# project-nixie.net
KiCad netlist of a schematic drawn in EAGLE
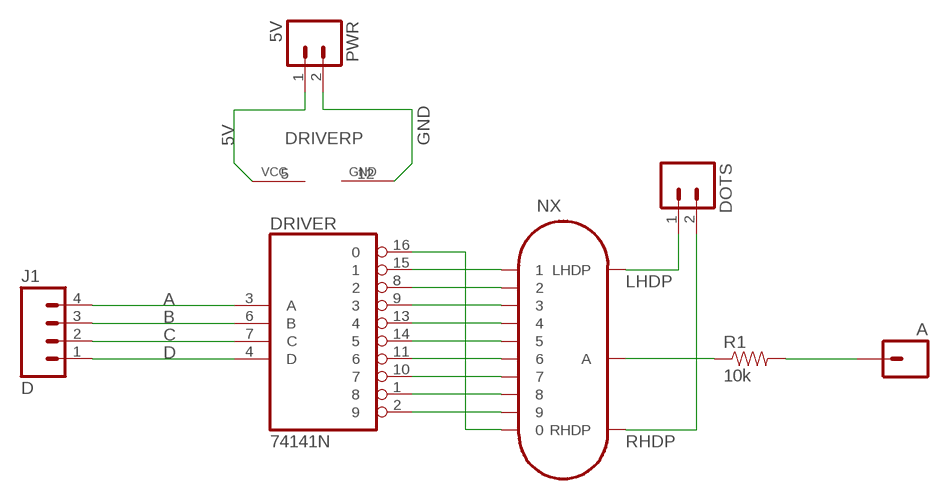
[diagram p0: schematic, sheet 1]

(export (version "E")
  (design (tool "Eeschema 10.0.6"))
  (components
    (comp (ref "A")
      (value "M01PTH")
      (footprint "eagle-import:1X01")
      (libsource (lib "eagle-import") (part "M01PTH"))
    )
    (comp (ref "DOTS")
      (value "M02PTH")
      (footprint "eagle-import:1X02")
      (libsource (lib "eagle-import") (part "M02PTH"))
    )
    (comp (ref "DRIVER")
      (value "74141N")
      (footprint "eagle-import:DIL16")
      (libsource (lib "eagle-import") (part "74141N"))
    )
    (comp (ref "J1")
      (value "D")
      (footprint "eagle-import:1X04_LOCK")
      (libsource (lib "eagle-import") (part "M04LOCK"))
    )
    (comp (ref "NX")
      (value "IN-14")
      (footprint "eagle-import:IN-14")
      (libsource (lib "eagle-import") (part "IN-14"))
    )
    (comp (ref "PWR")
      (value "5V")
      (footprint "eagle-import:1X02_LOCK")
      (libsource (lib "eagle-import") (part "M02LOCK"))
    )
    (comp (ref "R1")
      (value "10k")
      (footprint "eagle-import:AXIAL-0.3")
      (libsource (lib "eagle-import") (part "RESISTORAXIAL-0.3"))
    )
  )
  (nets
    (net (code "1") (name "/5V") (class "Default")
      (node (ref "DRIVER") (pin "5") (pinfunction "VCC_5") (pintype "power_in"))
      (node (ref "PWR") (pin "1") (pinfunction "1_1") (pintype "passive"))
    )
    (net (code "2") (name "/A") (class "Default")
      (node (ref "DRIVER") (pin "3") (pinfunction "A_3") (pintype "input"))
      (node (ref "J1") (pin "4") (pinfunction "4_4") (pintype "passive"))
    )
    (net (code "3") (name "/B") (class "Default")
      (node (ref "DRIVER") (pin "6") (pinfunction "B_6") (pintype "input"))
      (node (ref "J1") (pin "3") (pinfunction "3_3") (pintype "passive"))
    )
    (net (code "4") (name "/C") (class "Default")
      (node (ref "DRIVER") (pin "7") (pinfunction "C_7") (pintype "input"))
      (node (ref "J1") (pin "2") (pinfunction "2_2") (pintype "passive"))
    )
    (net (code "5") (name "/D") (class "Default")
      (node (ref "DRIVER") (pin "4") (pinfunction "D_4") (pintype "input"))
      (node (ref "J1") (pin "1") (pinfunction "1_1") (pintype "passive"))
    )
    (net (code "6") (name "/GND") (class "Default")
      (node (ref "DRIVER") (pin "12") (pinfunction "GND_12") (pintype "power_in"))
      (node (ref "PWR") (pin "2") (pinfunction "2_2") (pintype "passive"))
    )
    (net (code "7") (name "/LHDP") (class "Default")
      (node (ref "DOTS") (pin "1") (pinfunction "1_1") (pintype "passive"))
      (node (ref "NX") (pin "LHDP") (pinfunction "LHDP_LHDP") (pintype "bidirectional"))
    )
    (net (code "8") (name "/RHDP") (class "Default")
      (node (ref "DOTS") (pin "2") (pinfunction "2_2") (pintype "passive"))
      (node (ref "NX") (pin "RHDP") (pinfunction "RHDP_RHDP") (pintype "bidirectional"))
    )
    (net (code "9") (name "Net-(DRIVERA-0)") (class "Default")
      (node (ref "DRIVER") (pin "16") (pinfunction "0_16") (pintype "open_collector"))
      (node (ref "NX") (pin "0") (pinfunction "0_0") (pintype "bidirectional"))
    )
    (net (code "10") (name "Net-(DRIVERA-1)") (class "Default")
      (node (ref "DRIVER") (pin "15") (pinfunction "1_15") (pintype "open_collector"))
      (node (ref "NX") (pin "1") (pinfunction "1_1") (pintype "bidirectional"))
    )
    (net (code "11") (name "Net-(DRIVERA-2)") (class "Default")
      (node (ref "DRIVER") (pin "8") (pinfunction "2_8") (pintype "open_collector"))
      (node (ref "NX") (pin "2") (pinfunction "2_2") (pintype "bidirectional"))
    )
    (net (code "12") (name "Net-(DRIVERA-3)") (class "Default")
      (node (ref "DRIVER") (pin "9") (pinfunction "3_9") (pintype "open_collector"))
      (node (ref "NX") (pin "3") (pinfunction "3_3") (pintype "bidirectional"))
    )
    (net (code "13") (name "Net-(DRIVERA-4)") (class "Default")
      (node (ref "DRIVER") (pin "13") (pinfunction "4_13") (pintype "open_collector"))
      (node (ref "NX") (pin "4") (pinfunction "4_4") (pintype "bidirectional"))
    )
    (net (code "14") (name "Net-(DRIVERA-5)") (class "Default")
      (node (ref "DRIVER") (pin "14") (pinfunction "5_14") (pintype "open_collector"))
      (node (ref "NX") (pin "5") (pinfunction "5_5") (pintype "bidirectional"))
    )
    (net (code "15") (name "Net-(DRIVERA-6)") (class "Default")
      (node (ref "DRIVER") (pin "11") (pinfunction "6_11") (pintype "open_collector"))
      (node (ref "NX") (pin "6") (pinfunction "6_6") (pintype "bidirectional"))
    )
    (net (code "16") (name "Net-(DRIVERA-7)") (class "Default")
      (node (ref "DRIVER") (pin "10") (pinfunction "7_10") (pintype "open_collector"))
      (node (ref "NX") (pin "7") (pinfunction "7_7") (pintype "bidirectional"))
    )
    (net (code "17") (name "Net-(DRIVERA-8)") (class "Default")
      (node (ref "DRIVER") (pin "1") (pinfunction "8_1") (pintype "open_collector"))
      (node (ref "NX") (pin "8") (pinfunction "8_8") (pintype "bidirectional"))
    )
    (net (code "18") (name "Net-(DRIVERA-9)") (class "Default")
      (node (ref "DRIVER") (pin "2") (pinfunction "9_2") (pintype "open_collector"))
      (node (ref "NX") (pin "9") (pinfunction "9_9") (pintype "bidirectional"))
    )
    (net (code "19") (name "Net-(R1-1)") (class "Default")
      (node (ref "NX") (pin "A") (pinfunction "A_A") (pintype "bidirectional"))
      (node (ref "R1") (pin "P$1") (pinfunction "1_P$1") (pintype "passive"))
    )
    (net (code "20") (name "Net-(R1-2)") (class "Default")
      (node (ref "A") (pin "1") (pinfunction "1_1") (pintype "passive"))
      (node (ref "R1") (pin "P$2") (pinfunction "2_P$2") (pintype "passive"))
    )
  )
)
